# DiffController.net
KiCad netlist of a schematic drawn in EAGLE
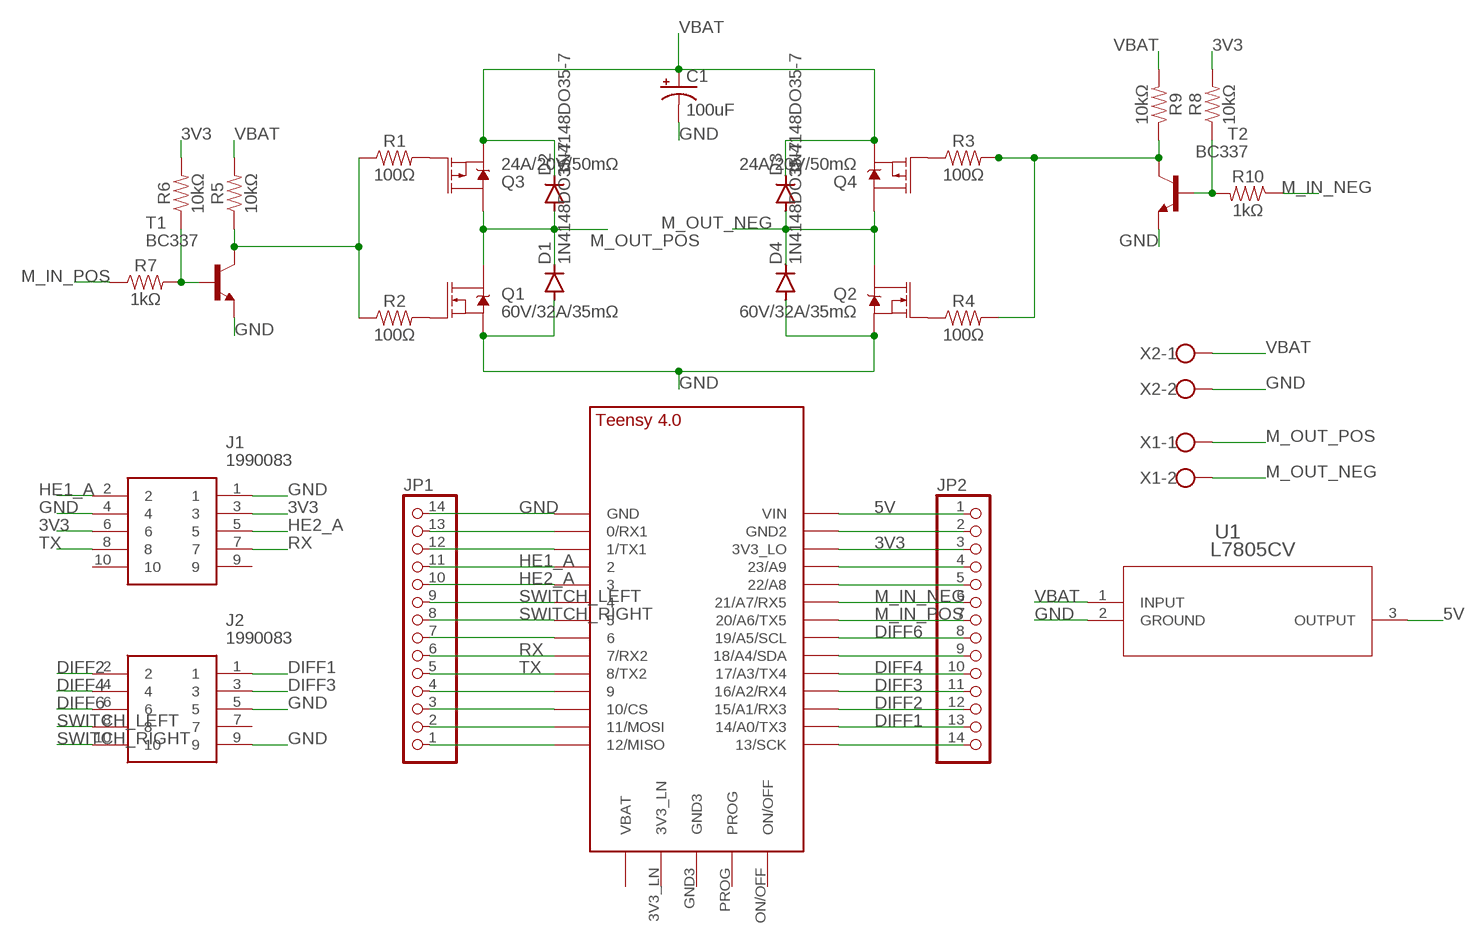
[diagram p0: schematic, sheet 1]

(export (version "E")
  (design (tool "Eeschema 10.0.6"))
  (components
    (comp (ref "C1")
      (value "100uF")
      (footprint "eagle-import:CPOL-RADIAL-2.5MM-6.5MM")
      (libsource (lib "eagle-import") (part "100UF-POLAR-RADIAL-2.5MM-25V-20%"))
    )
    (comp (ref "D1")
      (value "1N4148DO35-7")
      (footprint "eagle-import:DO35-7")
      (libsource (lib "eagle-import") (part "1N4148DO35-7"))
    )
    (comp (ref "D2")
      (value "1N4148DO35-7")
      (footprint "eagle-import:DO35-7")
      (libsource (lib "eagle-import") (part "1N4148DO35-7"))
    )
    (comp (ref "D3")
      (value "1N4148DO35-7")
      (footprint "eagle-import:DO35-7")
      (libsource (lib "eagle-import") (part "1N4148DO35-7"))
    )
    (comp (ref "D4")
      (value "1N4148DO35-7")
      (footprint "eagle-import:DO35-7")
      (libsource (lib "eagle-import") (part "1N4148DO35-7"))
    )
    (comp (ref "J1")
      (value "1990083")
      (footprint "eagle-import:1990083")
      (fields (field (name "MOUSER_PART_NUMBER") "651-1990083"))
      (libsource (lib "eagle-import") (part "1990083"))
    )
    (comp (ref "J2")
      (value "1990083")
      (footprint "eagle-import:1990083")
      (fields (field (name "MOUSER_PART_NUMBER") "651-1990083"))
      (libsource (lib "eagle-import") (part "1990083"))
    )
    (comp (ref "JP1")
      (value "PINHD-1X14")
      (footprint "eagle-import:1X14")
      (libsource (lib "eagle-import") (part "PINHD-1X14"))
    )
    (comp (ref "JP2")
      (value "PINHD-1X14")
      (footprint "eagle-import:1X14")
      (libsource (lib "eagle-import") (part "PINHD-1X14"))
    )
    (comp (ref "Q1")
      (value "60V/32A/35mΩ")
      (footprint "eagle-import:TO220V")
      (libsource (lib "eagle-import") (part "MOSFET-NCH-FQP30N06L"))
    )
    (comp (ref "Q2")
      (value "60V/32A/35mΩ")
      (footprint "eagle-import:TO220V")
      (libsource (lib "eagle-import") (part "MOSFET-NCH-FQP30N06L"))
    )
    (comp (ref "Q3")
      (value "24A/20V/50mΩ")
      (footprint "eagle-import:TO220V")
      (libsource (lib "eagle-import") (part "MOSFET_PCH-NDP6020P"))
    )
    (comp (ref "Q4")
      (value "24A/20V/50mΩ")
      (footprint "eagle-import:TO220V")
      (libsource (lib "eagle-import") (part "MOSFET_PCH-NDP6020P"))
    )
    (comp (ref "R1")
      (value "100Ω")
      (footprint "eagle-import:AXIAL-0.3")
      (libsource (lib "eagle-import") (part "RESISTORAXIAL-0.3"))
    )
    (comp (ref "R2")
      (value "100Ω")
      (footprint "eagle-import:AXIAL-0.3")
      (libsource (lib "eagle-import") (part "RESISTORAXIAL-0.3"))
    )
    (comp (ref "R3")
      (value "100Ω")
      (footprint "eagle-import:AXIAL-0.3")
      (libsource (lib "eagle-import") (part "RESISTORAXIAL-0.3"))
    )
    (comp (ref "R4")
      (value "100Ω")
      (footprint "eagle-import:AXIAL-0.3")
      (libsource (lib "eagle-import") (part "RESISTORAXIAL-0.3"))
    )
    (comp (ref "R5")
      (value "10kΩ")
      (footprint "eagle-import:AXIAL-0.3")
      (libsource (lib "eagle-import") (part "RESISTORAXIAL-0.3"))
    )
    (comp (ref "R6")
      (value "10kΩ")
      (footprint "eagle-import:AXIAL-0.3")
      (libsource (lib "eagle-import") (part "RESISTORAXIAL-0.3"))
    )
    (comp (ref "R7")
      (value "1kΩ")
      (footprint "eagle-import:AXIAL-0.3")
      (libsource (lib "eagle-import") (part "RESISTORAXIAL-0.3"))
    )
    (comp (ref "R8")
      (value "10kΩ")
      (footprint "eagle-import:AXIAL-0.3")
      (libsource (lib "eagle-import") (part "RESISTORAXIAL-0.3"))
    )
    (comp (ref "R9")
      (value "10kΩ")
      (footprint "eagle-import:AXIAL-0.3")
      (libsource (lib "eagle-import") (part "RESISTORAXIAL-0.3"))
    )
    (comp (ref "R10")
      (value "1kΩ")
      (footprint "eagle-import:AXIAL-0.3")
      (libsource (lib "eagle-import") (part "RESISTORAXIAL-0.3"))
    )
    (comp (ref "T1")
      (value "BC337")
      (footprint "eagle-import:TO92")
      (libsource (lib "eagle-import") (part "BC337"))
    )
    (comp (ref "T2")
      (value "BC337")
      (footprint "eagle-import:TO92")
      (libsource (lib "eagle-import") (part "BC337"))
    )
    (comp (ref "U$2")
      (value "TEENSY_4.0_EXPANDED_1")
      (footprint "eagle-import:TEENSY_4.0_EXPANDED_1")
      (libsource (lib "eagle-import") (part "TEENSY_4.0_EXPANDED_1"))
    )
    (comp (ref "U1")
      (value "L7805CV")
      (footprint "eagle-import:TO-220_STM")
      (libsource (lib "eagle-import") (part "L7805CV"))
    )
    (comp (ref "X1")
      (value "W237-102")
      (footprint "eagle-import:W237-102")
      (fields (field (name "MPN") "237-102"))
      (libsource (lib "eagle-import") (part "W237-102"))
    )
    (comp (ref "X2")
      (value "W237-102")
      (footprint "eagle-import:W237-102")
      (fields (field (name "MPN") "237-102"))
      (libsource (lib "eagle-import") (part "W237-102"))
    )
  )
  (nets
    (net (code "1") (name "/3V3") (class "Default")
      (node (ref "J1") (pin "3") (pinfunction "3_3") (pintype "bidirectional"))
      (node (ref "J1") (pin "6") (pinfunction "6_6") (pintype "bidirectional"))
      (node (ref "JP2") (pin "3") (pinfunction "3_3") (pintype "passive"))
      (node (ref "R6") (pin "P$2") (pinfunction "2_P$2") (pintype "passive"))
      (node (ref "R8") (pin "P$2") (pinfunction "2_P$2") (pintype "passive"))
      (node (ref "U$2") (pin "3V3_LO") (pinfunction "3V3_LO_3V3_LO") (pintype "bidirectional"))
    )
    (net (code "2") (name "/5V") (class "Default")
      (node (ref "JP2") (pin "1") (pinfunction "1_1") (pintype "passive"))
      (node (ref "U$2") (pin "VIN") (pinfunction "VIN_VIN") (pintype "bidirectional"))
      (node (ref "U1") (pin "3") (pinfunction "OUTPUT_3") (pintype "output"))
    )
    (net (code "3") (name "/DIFF1") (class "Default")
      (node (ref "J2") (pin "1") (pinfunction "1_1") (pintype "bidirectional"))
      (node (ref "JP2") (pin "13") (pinfunction "13_13") (pintype "passive"))
      (node (ref "U$2") (pin "14/A0") (pinfunction "14/A0/TX3_14/A0") (pintype "bidirectional"))
    )
    (net (code "4") (name "/DIFF2") (class "Default")
      (node (ref "J2") (pin "2") (pinfunction "2_2") (pintype "bidirectional"))
      (node (ref "JP2") (pin "12") (pinfunction "12_12") (pintype "passive"))
      (node (ref "U$2") (pin "15/A1") (pinfunction "15/A1/RX3_15/A1") (pintype "bidirectional"))
    )
    (net (code "5") (name "/DIFF3") (class "Default")
      (node (ref "J2") (pin "3") (pinfunction "3_3") (pintype "bidirectional"))
      (node (ref "JP2") (pin "11") (pinfunction "11_11") (pintype "passive"))
      (node (ref "U$2") (pin "16/A2") (pinfunction "16/A2/RX4_16/A2") (pintype "bidirectional"))
    )
    (net (code "6") (name "/DIFF4") (class "Default")
      (node (ref "J2") (pin "4") (pinfunction "4_4") (pintype "bidirectional"))
      (node (ref "JP2") (pin "10") (pinfunction "10_10") (pintype "passive"))
      (node (ref "U$2") (pin "17/A3") (pinfunction "17/A3/TX4_17/A3") (pintype "bidirectional"))
    )
    (net (code "7") (name "/DIFF6") (class "Default")
      (node (ref "J2") (pin "6") (pinfunction "6_6") (pintype "bidirectional"))
      (node (ref "JP2") (pin "8") (pinfunction "8_8") (pintype "passive"))
      (node (ref "U$2") (pin "19/A5/SCL") (pinfunction "19/A5/SCL_19/A5/SCL") (pintype "bidirectional"))
    )
    (net (code "8") (name "/GND") (class "Default")
      (node (ref "C1") (pin "2") (pinfunction "-_2") (pintype "passive"))
      (node (ref "D1") (pin "A") (pinfunction "A_A") (pintype "passive"))
      (node (ref "D4") (pin "A") (pinfunction "A_A") (pintype "passive"))
      (node (ref "J1") (pin "1") (pinfunction "1_1") (pintype "bidirectional"))
      (node (ref "J1") (pin "4") (pinfunction "4_4") (pintype "bidirectional"))
      (node (ref "J2") (pin "5") (pinfunction "5_5") (pintype "bidirectional"))
      (node (ref "J2") (pin "9") (pinfunction "9_9") (pintype "bidirectional"))
      (node (ref "JP1") (pin "14") (pinfunction "14_14") (pintype "passive"))
      (node (ref "Q1") (pin "3") (pinfunction "S_3") (pintype "bidirectional"))
      (node (ref "Q2") (pin "3") (pinfunction "S_3") (pintype "bidirectional"))
      (node (ref "T1") (pin "1") (pinfunction "E_1") (pintype "passive"))
      (node (ref "T2") (pin "1") (pinfunction "E_1") (pintype "passive"))
      (node (ref "U$2") (pin "GND") (pinfunction "GND_GND") (pintype "bidirectional"))
      (node (ref "U1") (pin "2") (pinfunction "GROUND_2") (pintype "passive"))
      (node (ref "X2") (pin "2") (pinfunction "KL_2") (pintype "passive"))
    )
    (net (code "9") (name "/HE1_A") (class "Default")
      (node (ref "J1") (pin "2") (pinfunction "2_2") (pintype "bidirectional"))
      (node (ref "JP1") (pin "11") (pinfunction "11_11") (pintype "passive"))
      (node (ref "U$2") (pin "2") (pinfunction "2_2") (pintype "bidirectional"))
    )
    (net (code "10") (name "/HE2_A") (class "Default")
      (node (ref "J1") (pin "5") (pinfunction "5_5") (pintype "bidirectional"))
      (node (ref "JP1") (pin "10") (pinfunction "10_10") (pintype "passive"))
      (node (ref "U$2") (pin "3/CANTX") (pinfunction "3_3/CANTX") (pintype "bidirectional"))
    )
    (net (code "11") (name "/M_IN_NEG") (class "Default")
      (node (ref "JP2") (pin "6") (pinfunction "6_6") (pintype "passive"))
      (node (ref "R10") (pin "P$1") (pinfunction "1_P$1") (pintype "passive"))
      (node (ref "U$2") (pin "21/A7") (pinfunction "21/A7/RX5_21/A7") (pintype "bidirectional"))
    )
    (net (code "12") (name "/M_IN_POS") (class "Default")
      (node (ref "JP2") (pin "7") (pinfunction "7_7") (pintype "passive"))
      (node (ref "R7") (pin "P$1") (pinfunction "1_P$1") (pintype "passive"))
      (node (ref "U$2") (pin "20/A6") (pinfunction "20/A6/TX5_20/A6") (pintype "bidirectional"))
    )
    (net (code "13") (name "/M_OUT_NEG") (class "Default")
      (node (ref "D3") (pin "A") (pinfunction "A_A") (pintype "passive"))
      (node (ref "D4") (pin "C") (pinfunction "C_C") (pintype "passive"))
      (node (ref "Q2") (pin "2") (pinfunction "D_2") (pintype "bidirectional"))
      (node (ref "Q4") (pin "2") (pinfunction "D_2") (pintype "bidirectional"))
      (node (ref "X1") (pin "2") (pinfunction "KL_2") (pintype "passive"))
    )
    (net (code "14") (name "/M_OUT_POS") (class "Default")
      (node (ref "D1") (pin "C") (pinfunction "C_C") (pintype "passive"))
      (node (ref "D2") (pin "A") (pinfunction "A_A") (pintype "passive"))
      (node (ref "Q1") (pin "2") (pinfunction "D_2") (pintype "bidirectional"))
      (node (ref "Q3") (pin "2") (pinfunction "D_2") (pintype "bidirectional"))
      (node (ref "X1") (pin "1") (pinfunction "KL_1") (pintype "passive"))
    )
    (net (code "15") (name "/RX") (class "Default")
      (node (ref "J1") (pin "7") (pinfunction "7_7") (pintype "bidirectional"))
      (node (ref "JP1") (pin "6") (pinfunction "6_6") (pintype "passive"))
      (node (ref "U$2") (pin "7") (pinfunction "7/RX2_7") (pintype "bidirectional"))
    )
    (net (code "16") (name "/SWITCH_LEFT") (class "Default")
      (node (ref "J2") (pin "8") (pinfunction "8_8") (pintype "bidirectional"))
      (node (ref "JP1") (pin "9") (pinfunction "9_9") (pintype "passive"))
      (node (ref "U$2") (pin "4/CANRX") (pinfunction "4_4/CANRX") (pintype "bidirectional"))
    )
    (net (code "17") (name "/SWITCH_RIGHT") (class "Default")
      (node (ref "J2") (pin "10") (pinfunction "10_10") (pintype "bidirectional"))
      (node (ref "JP1") (pin "8") (pinfunction "8_8") (pintype "passive"))
      (node (ref "U$2") (pin "5") (pinfunction "5_5") (pintype "bidirectional"))
    )
    (net (code "18") (name "/TX") (class "Default")
      (node (ref "J1") (pin "8") (pinfunction "8_8") (pintype "bidirectional"))
      (node (ref "JP1") (pin "5") (pinfunction "5_5") (pintype "passive"))
      (node (ref "U$2") (pin "8") (pinfunction "8/TX2_8") (pintype "bidirectional"))
    )
    (net (code "19") (name "/VBAT") (class "Default")
      (node (ref "C1") (pin "1") (pinfunction "+_1") (pintype "passive"))
      (node (ref "D2") (pin "C") (pinfunction "C_C") (pintype "passive"))
      (node (ref "D3") (pin "C") (pinfunction "C_C") (pintype "passive"))
      (node (ref "Q3") (pin "3") (pinfunction "S_3") (pintype "bidirectional"))
      (node (ref "Q4") (pin "3") (pinfunction "S_3") (pintype "bidirectional"))
      (node (ref "R5") (pin "P$2") (pinfunction "2_P$2") (pintype "passive"))
      (node (ref "R9") (pin "P$2") (pinfunction "2_P$2") (pintype "passive"))
      (node (ref "U1") (pin "1") (pinfunction "INPUT_1") (pintype "input"))
      (node (ref "X2") (pin "1") (pinfunction "KL_1") (pintype "passive"))
    )
    (net (code "20") (name "Net-(JP1-Pad1)") (class "Default")
      (node (ref "JP1") (pin "1") (pinfunction "1_1") (pintype "passive"))
      (node (ref "U$2") (pin "12/MISO") (pinfunction "12/MISO_12/MISO") (pintype "bidirectional"))
    )
    (net (code "21") (name "Net-(JP1-Pad2)") (class "Default")
      (node (ref "JP1") (pin "2") (pinfunction "2_2") (pintype "passive"))
      (node (ref "U$2") (pin "11/MOSI") (pinfunction "11/MOSI_11/MOSI") (pintype "bidirectional"))
    )
    (net (code "22") (name "Net-(JP1-Pad3)") (class "Default")
      (node (ref "JP1") (pin "3") (pinfunction "3_3") (pintype "passive"))
      (node (ref "U$2") (pin "10/CS") (pinfunction "10/CS_10/CS") (pintype "bidirectional"))
    )
    (net (code "23") (name "Net-(JP1-Pad7)") (class "Default")
      (node (ref "JP1") (pin "7") (pinfunction "7_7") (pintype "passive"))
      (node (ref "U$2") (pin "6") (pinfunction "6_6") (pintype "bidirectional"))
    )
    (net (code "24") (name "Net-(JP2-Pad2)") (class "Default")
      (node (ref "JP2") (pin "2") (pinfunction "2_2") (pintype "passive"))
      (node (ref "U$2") (pin "GND2") (pinfunction "GND2_GND2") (pintype "bidirectional"))
    )
    (net (code "25") (name "Net-(JP2-Pad4)") (class "Default")
      (node (ref "JP2") (pin "4") (pinfunction "4_4") (pintype "passive"))
      (node (ref "U$2") (pin "23/A9") (pinfunction "23/A9_23/A9") (pintype "bidirectional"))
    )
    (net (code "26") (name "Net-(JP2-Pad5)") (class "Default")
      (node (ref "JP2") (pin "5") (pinfunction "5_5") (pintype "passive"))
      (node (ref "U$2") (pin "22/A8") (pinfunction "22/A8_22/A8") (pintype "bidirectional"))
    )
    (net (code "27") (name "Net-(JP2-Pad9)") (class "Default")
      (node (ref "JP2") (pin "9") (pinfunction "9_9") (pintype "passive"))
      (node (ref "U$2") (pin "18/A4/SDA") (pinfunction "18/A4/SDA_18/A4/SDA") (pintype "bidirectional"))
    )
    (net (code "28") (name "Net-(JP2-Pad14)") (class "Default")
      (node (ref "JP2") (pin "14") (pinfunction "14_14") (pintype "passive"))
      (node (ref "U$2") (pin "13/SCK") (pinfunction "13/SCK_13/SCK") (pintype "bidirectional"))
    )
    (net (code "29") (name "Net-(Q1-G)") (class "Default")
      (node (ref "Q1") (pin "1") (pinfunction "G_1") (pintype "bidirectional"))
      (node (ref "R2") (pin "P$2") (pinfunction "2_P$2") (pintype "passive"))
    )
    (net (code "30") (name "Net-(Q2-G)") (class "Default")
      (node (ref "Q2") (pin "1") (pinfunction "G_1") (pintype "bidirectional"))
      (node (ref "R4") (pin "P$1") (pinfunction "1_P$1") (pintype "passive"))
    )
    (net (code "31") (name "Net-(Q3-G)") (class "Default")
      (node (ref "Q3") (pin "1") (pinfunction "G_1") (pintype "bidirectional"))
      (node (ref "R1") (pin "P$2") (pinfunction "2_P$2") (pintype "passive"))
    )
    (net (code "32") (name "Net-(Q4-G)") (class "Default")
      (node (ref "Q4") (pin "1") (pinfunction "G_1") (pintype "bidirectional"))
      (node (ref "R3") (pin "P$1") (pinfunction "1_P$1") (pintype "passive"))
    )
    (net (code "33") (name "Net-(R1-1)") (class "Default")
      (node (ref "R1") (pin "P$1") (pinfunction "1_P$1") (pintype "passive"))
      (node (ref "R2") (pin "P$1") (pinfunction "1_P$1") (pintype "passive"))
      (node (ref "R5") (pin "P$1") (pinfunction "1_P$1") (pintype "passive"))
      (node (ref "T1") (pin "3") (pinfunction "C_3") (pintype "passive"))
    )
    (net (code "34") (name "Net-(R3-2)") (class "Default")
      (node (ref "R3") (pin "P$2") (pinfunction "2_P$2") (pintype "passive"))
      (node (ref "R4") (pin "P$2") (pinfunction "2_P$2") (pintype "passive"))
      (node (ref "R9") (pin "P$1") (pinfunction "1_P$1") (pintype "passive"))
      (node (ref "T2") (pin "3") (pinfunction "C_3") (pintype "passive"))
    )
    (net (code "35") (name "Net-(R6-1)") (class "Default")
      (node (ref "R6") (pin "P$1") (pinfunction "1_P$1") (pintype "passive"))
      (node (ref "R7") (pin "P$2") (pinfunction "2_P$2") (pintype "passive"))
      (node (ref "T1") (pin "2") (pinfunction "B_2") (pintype "passive"))
    )
    (net (code "36") (name "Net-(R10-2)") (class "Default")
      (node (ref "R10") (pin "P$2") (pinfunction "2_P$2") (pintype "passive"))
      (node (ref "R8") (pin "P$1") (pinfunction "1_P$1") (pintype "passive"))
      (node (ref "T2") (pin "2") (pinfunction "B_2") (pintype "passive"))
    )
    (net (code "37") (name "Net-(U$2-0{slash}RX1)") (class "Default")
      (node (ref "JP1") (pin "13") (pinfunction "13_13") (pintype "passive"))
      (node (ref "U$2") (pin "0/RX") (pinfunction "0/RX1_0/RX") (pintype "bidirectional"))
    )
    (net (code "38") (name "Net-(U$2-1{slash}TX1)") (class "Default")
      (node (ref "JP1") (pin "12") (pinfunction "12_12") (pintype "passive"))
      (node (ref "U$2") (pin "1/TX") (pinfunction "1/TX1_1/TX") (pintype "bidirectional"))
    )
    (net (code "39") (name "Net-(U$2-9)") (class "Default")
      (node (ref "JP1") (pin "4") (pinfunction "4_4") (pintype "passive"))
      (node (ref "U$2") (pin "9/CS") (pinfunction "9_9/CS") (pintype "bidirectional"))
    )
    (net (code "40") (name "unconnected-(J1-Pad9)") (class "Default")
      (node (ref "J1") (pin "9") (pinfunction "9_9") (pintype "bidirectional"))
    )
    (net (code "41") (name "unconnected-(J1-Pad10)") (class "Default")
      (node (ref "J1") (pin "10") (pinfunction "10_10") (pintype "bidirectional"))
    )
    (net (code "42") (name "unconnected-(J2-Pad7)") (class "Default")
      (node (ref "J2") (pin "7") (pinfunction "7_7") (pintype "bidirectional"))
    )
    (net (code "43") (name "unconnected-(U$2-Pad3V3_LN)") (class "Default")
      (node (ref "U$2") (pin "3V3_LN") (pinfunction "3V3_LN_3V3_LN") (pintype "bidirectional"))
    )
    (net (code "44") (name "unconnected-(U$2-PadGND3)") (class "Default")
      (node (ref "U$2") (pin "GND3") (pinfunction "GND3_GND3") (pintype "bidirectional"))
    )
    (net (code "45") (name "unconnected-(U$2-PadON{slash}OFF)") (class "Default")
      (node (ref "U$2") (pin "ON/OFF") (pinfunction "ON/OFF_ON/OFF") (pintype "bidirectional"))
    )
    (net (code "46") (name "unconnected-(U$2-PadPROG)") (class "Default")
      (node (ref "U$2") (pin "PROG") (pinfunction "PROG_PROG") (pintype "bidirectional"))
    )
    (net (code "47") (name "unconnected-(U$2-VBAT-PadVBAT\\)") (class "Default")
      (node (ref "U$2") (pin "VBAT\\") (pinfunction "VBAT_VBAT\\") (pintype "bidirectional"))
    )
  )
)
